# efr32_radio_interface.net
KiCad netlist of a schematic drawn in Altium Designer
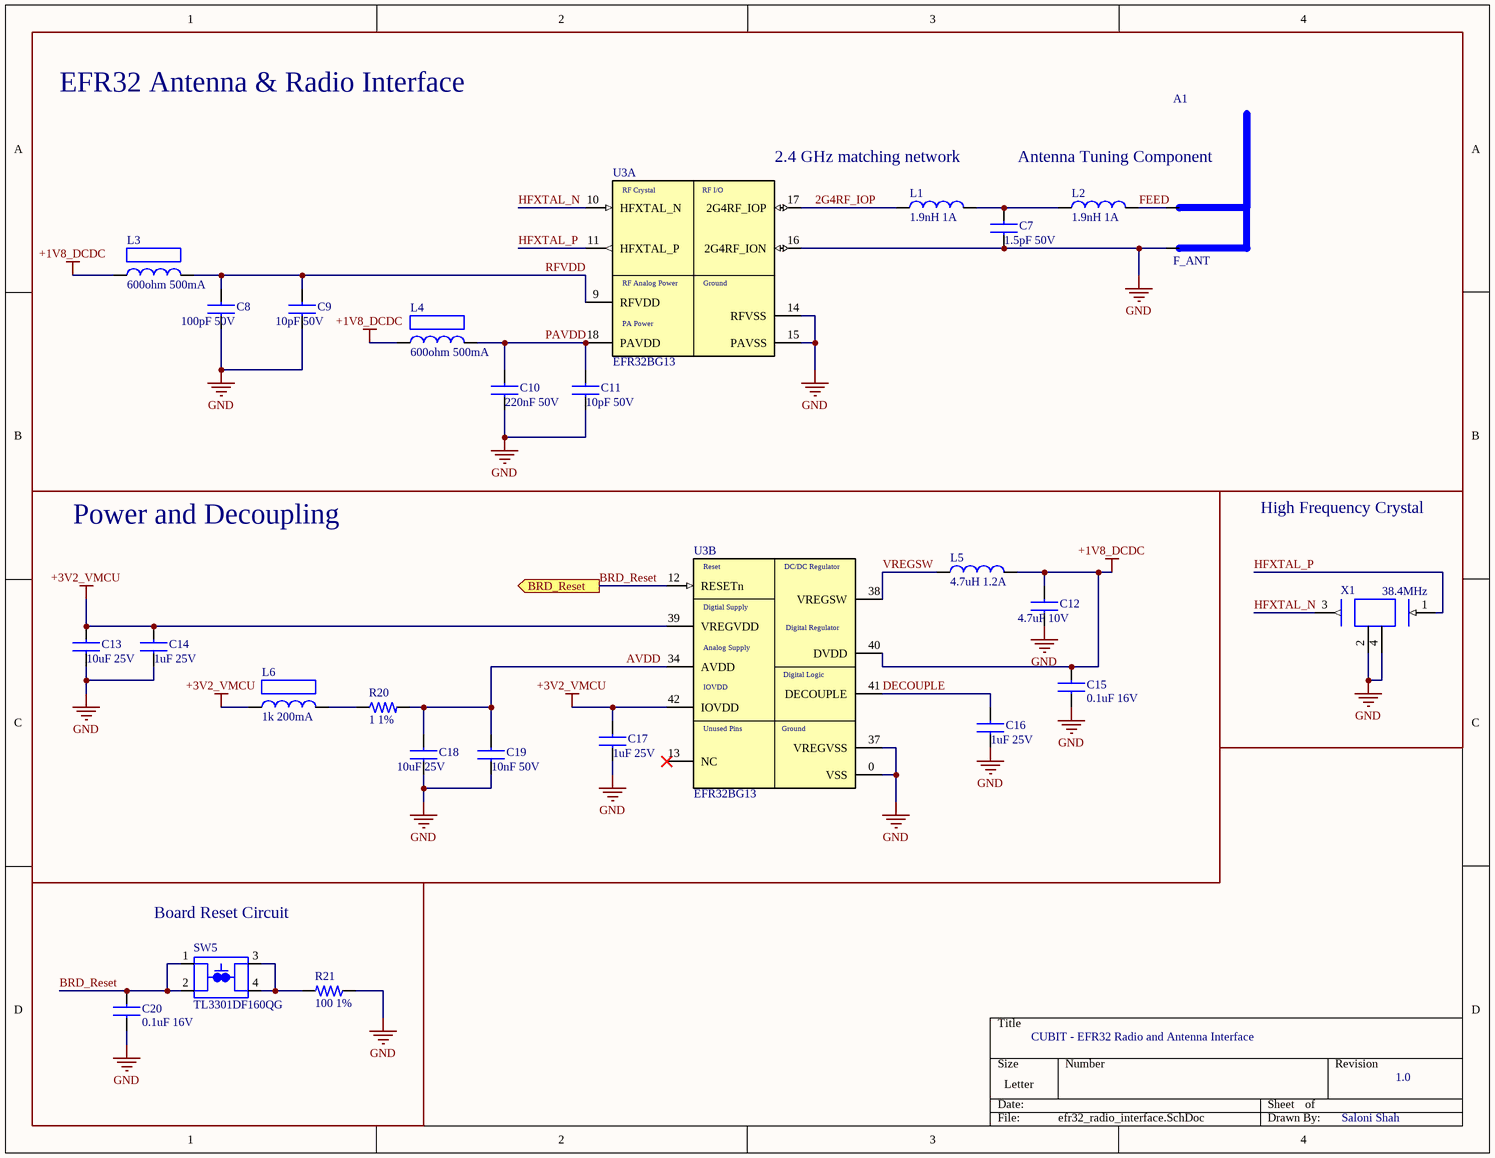
[diagram p0: efr32_radio_interface.SchDoc]

(export (version "E")
  (design (tool "Eeschema 10.0.6"))
  (components
    (comp (ref "A1")
      (value "F_ANT")
      (footprint "F_ANTENNA_FOOTPRINT")
      (libsource (lib "LPEDT_proj_lib") (part "F_ANT"))
    )
    (comp (ref "C7")
      (value "1.5pF 50V")
      (footprint "CAP_0402_1mm")
      (description "Cap Ceramic 1.5pF 50V C0G 5% Pad SMD 0402 125C Automotive T/R")
      (fields
        (field (name "MANUFACTURER") "Murata")
        (field (name "MANUFACTURER PART NUMBER") "GCM1555C1H1R5JA16D")
      )
      (libsource (lib "LPEDT_proj_lib") (part "GCM1555C1H1R5JA16D"))
    )
    (comp (ref "C8")
      (value "100pF 50V")
      (footprint "LPEDT_proj_lib:CAP_0805_02X125")
      (description "Cap 0.1nF ±10% 50V X7R 0805")
      (fields
        (field (name "MANUFACTURER") "Yageo")
        (field (name "MANUFACTURER PART NUMBER") "CC0805KRX7R9BB101")
      )
      (libsource (lib "LPEDT_proj_lib") (part "CC0805KRX7R9BB101"))
    )
    (comp (ref "C9")
      (value "10pF 50V")
      (footprint "LPEDT_proj_lib:CAP_0805_02X125")
      (description "Cap Ceramic 10pF 50V X7R 10% SMD 0805 125°C Paper T/R")
      (fields
        (field (name "MANUFACTURER") "KEMET")
        (field (name "MANUFACTURER PART NUMBER") "C0805C100K5RACTU")
      )
      (libsource (lib "LPEDT_proj_lib") (part "C0805C100K5RACTU"))
    )
    (comp (ref "C10")
      (value "220nF 50V")
      (footprint "LPEDT_proj_lib:CAP_0805_02X125")
      (description "Cap 220nF ±10% 50V X7R 0805")
      (fields
        (field (name "MANUFACTURER") "Yageo")
        (field (name "MANUFACTURER PART NUMBER") "CC0805KKX7R9BB224")
      )
      (libsource (lib "LPEDT_proj_lib") (part "CC0805KKX7R9BB224"))
    )
    (comp (ref "C11")
      (value "10pF 50V")
      (footprint "LPEDT_proj_lib:CAP_0805_02X125")
      (description "Cap Ceramic 10pF 50V X7R 10% SMD 0805 125°C Paper T/R")
      (fields
        (field (name "MANUFACTURER") "KEMET")
        (field (name "MANUFACTURER PART NUMBER") "C0805C100K5RACTU")
      )
      (libsource (lib "LPEDT_proj_lib") (part "C0805C100K5RACTU"))
    )
    (comp (ref "C12")
      (value "4.7uF 10V")
      (footprint "LPEDT_proj_lib:CAP_0603_1MM")
      (description "Cap CL10 Series 4.7 uF 10 V ±10 % Tolerance X5R SMT Multilayer Ceramic Capacitor")
      (fields
        (field (name "MANUFACTURER") "Samsung")
        (field (name "MANUFACTURER PART NUMBER") "CL10A475KP8NNNC")
      )
      (libsource (lib "LPEDT_proj_lib") (part "CL10A475KP8NNNC"))
    )
    (comp (ref "C13")
      (value "10uF 25V")
      (footprint "LPEDT_proj_lib:CAP_0805_02X125")
      (description "Cap 0805 25 V 10 uF ±20% Tolerance X5R Monolithic Ceramic Chip Capacitor")
      (fields
        (field (name "MANUFACTURER") "Murata")
        (field (name "MANUFACTURER PART NUMBER") "GRM21BR61E106KA73K")
      )
      (libsource (lib "LPEDT_proj_lib") (part "GRM21BR61E106KA73K"))
    )
    (comp (ref "C14")
      (value "1uF 25V")
      (footprint "LPEDT_proj_lib:CAP_0805_02X125")
      (description "Cap 1 µF ±10% 25V Ceramic Capacitor X5R 0805 (2012 Metric)")
      (fields
        (field (name "MANUFACTURER") "Murata")
        (field (name "MANUFACTURER PART NUMBER") "GRM216R61E105KA12D")
      )
      (libsource (lib "LPEDT_proj_lib") (part "GRM216R61E105KA12D"))
    )
    (comp (ref "C15")
      (value "0.1uF 16V")
      (footprint "LPEDT_proj_lib:CAP_0603_1MM")
      (description "Cap Ceramic 0.1uF 16V X7R 10% SMD 0603 125°C Paper T/R")
      (fields
        (field (name "MANUFACTURER") "KEMET")
        (field (name "MANUFACTURER PART NUMBER") "C0805C104K4RACAUTO")
      )
      (libsource (lib "LPEDT_proj_lib") (part "C0805C104K4RACAUTO"))
    )
    (comp (ref "C16")
      (value "1uF 25V")
      (footprint "LPEDT_proj_lib:CAP_0805_02X125")
      (description "Cap 1 µF ±10% 25V Ceramic Capacitor X5R 0805 (2012 Metric)")
      (fields
        (field (name "MANUFACTURER") "Murata")
        (field (name "MANUFACTURER PART NUMBER") "GRM216R61E105KA12D")
      )
      (libsource (lib "LPEDT_proj_lib") (part "GRM216R61E105KA12D"))
    )
    (comp (ref "C17")
      (value "1uF 25V")
      (footprint "LPEDT_proj_lib:CAP_0805_02X125")
      (description "Cap 1 µF ±10% 25V Ceramic Capacitor X5R 0805 (2012 Metric)")
      (fields
        (field (name "MANUFACTURER") "Murata")
        (field (name "MANUFACTURER PART NUMBER") "GRM216R61E105KA12D")
      )
      (libsource (lib "LPEDT_proj_lib") (part "GRM216R61E105KA12D"))
    )
    (comp (ref "C18")
      (value "10uF 25V")
      (footprint "LPEDT_proj_lib:CAP_0805_02X125")
      (description "Cap 0805 25 V 10 uF ±20% Tolerance X5R Monolithic Ceramic Chip Capacitor")
      (fields
        (field (name "MANUFACTURER") "Murata")
        (field (name "MANUFACTURER PART NUMBER") "GRM21BR61E106KA73K")
      )
      (libsource (lib "LPEDT_proj_lib") (part "GRM21BR61E106KA73K"))
    )
    (comp (ref "C19")
      (value "10nF 50V")
      (footprint "LPEDT_proj_lib:CAP_0805_02X125")
      (description "Cap 10nF ±10% 50V X7R 0805")
      (fields
        (field (name "MANUFACTURER") "Samsung")
        (field (name "MANUFACTURER PART NUMBER") "CL21B103KBCNNNC")
      )
      (libsource (lib "LPEDT_proj_lib") (part "CL21B103KBCNNNC"))
    )
    (comp (ref "C20")
      (value "0.1uF 16V")
      (footprint "LPEDT_proj_lib:CAP_0603_1MM")
      (description "Cap Ceramic 0.1uF 16V X7R 10% SMD 0603 125°C Paper T/R")
      (fields
        (field (name "MANUFACTURER") "KEMET")
        (field (name "MANUFACTURER PART NUMBER") "C0805C104K4RACAUTO")
      )
      (libsource (lib "LPEDT_proj_lib") (part "C0805C104K4RACAUTO"))
    )
    (comp (ref "L1")
      (value "1.9nH 1A")
      (footprint "CAP_0402_1mm")
      (description "Inductor Chip 1.9nH 0.3nH Tolerance 2-Pin 0402 Paper T/R")
      (fields
        (field (name "MANUFACTURER") "Murata")
        (field (name "MANUFACTURER PART NUMBER") "LQG15WZ1N9S02D")
      )
      (libsource (lib "LPEDT_proj_lib") (part "LQG15WZ1N9S02D"))
    )
    (comp (ref "L2")
      (value "1.9nH 1A")
      (footprint "CAP_0402_1mm")
      (description "Inductor Chip 1.9nH 0.3nH Tolerance 2-Pin 0402 Paper T/R")
      (fields
        (field (name "MANUFACTURER") "Murata")
        (field (name "MANUFACTURER PART NUMBER") "LQG15WZ1N9S02D")
      )
      (libsource (lib "LPEDT_proj_lib") (part "LQG15WZ1N9S02D"))
    )
    (comp (ref "L3")
      (value "600ohm 500mA")
      (footprint "IND_FERRITE_0603_1.6x0.4")
      (description "Ferrite Beads 0603 600Ω ±25% DCR=0.38Ω 500mA")
      (fields
        (field (name "MANUFACTURER") "Murata")
        (field (name "MANUFACTURER PART NUMBER") "BLM18AG601SN1D")
      )
      (libsource (lib "LPEDT_proj_lib") (part "BLM18AG601SN1D"))
    )
    (comp (ref "L4")
      (value "600ohm 500mA")
      (footprint "IND_FERRITE_0603_1.6x0.4")
      (description "Ferrite Beads 0603 600Ω ±25% DCR=0.38Ω 500mA")
      (fields
        (field (name "MANUFACTURER") "Murata")
        (field (name "MANUFACTURER PART NUMBER") "BLM18AG601SN1D")
      )
      (libsource (lib "LPEDT_proj_lib") (part "BLM18AG601SN1D"))
    )
    (comp (ref "L5")
      (value "4.7uH 1.2A")
      (footprint "2_IND_32X25")
      (description "Inductor FIXED IND 4.7UH 1.2A 186 MOHM")
      (fields
        (field (name "MANUFACTURER") "Murata")
        (field (name "MANUFACTURER PART NUMBER") "LQH32PH4R7NNCL")
      )
      (libsource (lib "LPEDT_proj_lib") (part "LQH32PH4R7NNCL"))
    )
    (comp (ref "L6")
      (value "1k 200mA")
      (footprint "LPEDT_proj_lib:CAP_0603_1MM")
      (description "Ferrite Beads WE-CBF 0603 SMD Bead 100MHz 1000Ohm 200mA")
      (fields
        (field (name "MANUFACTURER") "Wurth Electronics")
        (field (name "MANUFACTURER PART NUMBER") "74279266")
      )
      (libsource (lib "LPEDT_proj_lib") (part "74279266"))
    )
    (comp (ref "R20")
      (value "1 1%")
      (footprint "LPEDT_proj_lib:CAP_0603_1MM")
      (description "Res 1 Ohm 1% 1/10W ±200ppm/°C Molded SMD SMD Paper T/R")
      (fields
        (field (name "MANUFACTURER") "Yageo")
        (field (name "MANUFACTURER PART NUMBER") "RC0603FR-101RL")
      )
      (libsource (lib "LPEDT_proj_lib") (part "RC0603FR-101RL"))
    )
    (comp (ref "R21")
      (value "100 1%")
      (footprint "2_Chip_0603_RMCF")
      (description "Res 100 Ohm 1% 1/10W ±100ppm/°C Molded SMD SMD Paper T/R")
      (fields
        (field (name "MANUFACTURER") "Stackpole Electronics")
        (field (name "MANUFACTURER PART NUMBER") "RMCF0603FT100R")
      )
      (libsource (lib "LPEDT_proj_lib") (part "RMCF0603FT100R"))
    )
    (comp (ref "SW5")
      (value "TL3301DF160QG")
      (footprint "SW_TL3301DF160QG")
      (description "Tactile Switch SPST-NO Top Actuated Surface Mount")
      (fields (field (name "MF") "E-Switch"))
      (libsource (lib "LPEDT_proj_lib") (part "TL3301DF160QG"))
    )
    (comp (ref "U3")
      (value "EFR32BG13")
      (footprint "48-QFN_7x7")
      (description "Blue Gecko QFN48 2.4 G 19 dB BLE/Proprietary 512 kB 64 kB(RAM) 31GPIO")
      (fields
        (field (name "MANUFACTURER") "Silicon Labs")
        (field (name "MANUFACTURER PART NUMBER") "EFR32BG13P732F512GM48-D")
      )
      (libsource (lib "LPEDT_proj_lib") (part "EFR32BG13P732F512GM48-D"))
    )
    (comp (ref "X1")
      (value "38.4MHz")
      (footprint "OSC_38.4MHz")
      (description "Crystal 38.4000MHZ 10PF SMD")
      (fields
        (field (name "MANUFACTURER") "Raltron Electronics")
        (field (name "MANUFACTURER PART NUMBER") "RH100-38.400-10-F-1010-TR")
      )
      (libsource (lib "LPEDT_proj_lib") (part "RH100-38.400-10-F-1010-TR"))
    )
  )
  (nets
    (net (code "1") (name "+1V8_DCDC") (class "Default")
      (node (ref "C12") (pin "1") (pinfunction "1_1") (pintype "passive"))
      (node (ref "C15") (pin "1") (pinfunction "1_1") (pintype "passive"))
      (node (ref "L3") (pin "1") (pinfunction "1_1") (pintype "passive"))
      (node (ref "L4") (pin "1") (pinfunction "1_1") (pintype "passive"))
      (node (ref "L5") (pin "2") (pinfunction "2_2") (pintype "passive"))
      (node (ref "U3") (pin "40") (pinfunction "DVDD_40") (pintype "power_in"))
    )
    (net (code "2") (name "+3V2_VMCU") (class "Default")
      (node (ref "C13") (pin "1") (pinfunction "1_1") (pintype "passive"))
      (node (ref "C14") (pin "1") (pinfunction "1_1") (pintype "passive"))
      (node (ref "C17") (pin "1") (pinfunction "1_1") (pintype "passive"))
      (node (ref "L6") (pin "1") (pinfunction "1_1") (pintype "passive"))
      (node (ref "U3") (pin "39") (pinfunction "VREGVDD_39") (pintype "power_in"))
      (node (ref "U3") (pin "42") (pinfunction "IOVDD_42") (pintype "power_in"))
    )
    (net (code "3") (name "/2G4RF_IOP") (class "Default")
      (node (ref "L1") (pin "1") (pinfunction "1_1") (pintype "passive"))
      (node (ref "U3") (pin "17") (pinfunction "2G4RF_IOP_17") (pintype "bidirectional"))
    )
    (net (code "4") (name "/AVDD") (class "Default")
      (node (ref "C18") (pin "1") (pinfunction "1_1") (pintype "passive"))
      (node (ref "C19") (pin "1") (pinfunction "1_1") (pintype "passive"))
      (node (ref "R20") (pin "2") (pinfunction "2_2") (pintype "passive"))
      (node (ref "U3") (pin "34") (pinfunction "AVDD_34") (pintype "power_in"))
    )
    (net (code "5") (name "/BRD_Reset") (class "Default")
      (node (ref "C20") (pin "1") (pinfunction "1_1") (pintype "passive"))
      (node (ref "SW5") (pin "1") (pinfunction "1_1") (pintype "passive"))
      (node (ref "SW5") (pin "2") (pinfunction "2_2") (pintype "passive"))
      (node (ref "U3") (pin "12") (pinfunction "RESETn_12") (pintype "input"))
    )
    (net (code "6") (name "/DECOUPLE") (class "Default")
      (node (ref "C16") (pin "1") (pinfunction "1_1") (pintype "passive"))
      (node (ref "U3") (pin "41") (pinfunction "DECOUPLE_41") (pintype "power_in"))
    )
    (net (code "7") (name "/FEED") (class "Default")
      (node (ref "A1") (pin "FEED") (pinfunction "FEED_FEED") (pintype "passive"))
      (node (ref "L2") (pin "2") (pinfunction "2_2") (pintype "passive"))
    )
    (net (code "8") (name "/HFXTAL_N") (class "Default")
      (node (ref "U3") (pin "10") (pinfunction "HFXTAL_N_10") (pintype "input"))
      (node (ref "X1") (pin "3") (pintype "output"))
    )
    (net (code "9") (name "/HFXTAL_P") (class "Default")
      (node (ref "U3") (pin "11") (pinfunction "HFXTAL_P_11") (pintype "output"))
      (node (ref "X1") (pin "1") (pintype "input"))
    )
    (net (code "10") (name "/PAVDD") (class "Default")
      (node (ref "C10") (pin "1") (pinfunction "1_1") (pintype "passive"))
      (node (ref "C11") (pin "1") (pinfunction "1_1") (pintype "passive"))
      (node (ref "L4") (pin "2") (pinfunction "2_2") (pintype "passive"))
      (node (ref "U3") (pin "18") (pinfunction "PAVDD_18") (pintype "power_in"))
    )
    (net (code "11") (name "/RFVDD") (class "Default")
      (node (ref "C8") (pin "1") (pinfunction "1_1") (pintype "passive"))
      (node (ref "C9") (pin "1") (pinfunction "1_1") (pintype "passive"))
      (node (ref "L3") (pin "2") (pinfunction "2_2") (pintype "passive"))
      (node (ref "U3") (pin "9") (pinfunction "RFVDD_9") (pintype "power_in"))
    )
    (net (code "12") (name "/VREGSW") (class "Default")
      (node (ref "L5") (pin "1") (pinfunction "1_1") (pintype "passive"))
      (node (ref "U3") (pin "38") (pinfunction "VREGSW_38") (pintype "power_in"))
    )
    (net (code "13") (name "GND") (class "Default")
      (node (ref "A1") (pin "GND") (pinfunction "GND_GND") (pintype "passive"))
      (node (ref "C10") (pin "2") (pinfunction "2_2") (pintype "passive"))
      (node (ref "C11") (pin "2") (pinfunction "2_2") (pintype "passive"))
      (node (ref "C12") (pin "2") (pinfunction "2_2") (pintype "passive"))
      (node (ref "C13") (pin "2") (pinfunction "2_2") (pintype "passive"))
      (node (ref "C14") (pin "2") (pinfunction "2_2") (pintype "passive"))
      (node (ref "C15") (pin "2") (pinfunction "2_2") (pintype "passive"))
      (node (ref "C16") (pin "2") (pinfunction "2_2") (pintype "passive"))
      (node (ref "C17") (pin "2") (pinfunction "2_2") (pintype "passive"))
      (node (ref "C18") (pin "2") (pinfunction "2_2") (pintype "passive"))
      (node (ref "C19") (pin "2") (pinfunction "2_2") (pintype "passive"))
      (node (ref "C20") (pin "2") (pinfunction "2_2") (pintype "passive"))
      (node (ref "C7") (pin "2") (pinfunction "2_2") (pintype "passive"))
      (node (ref "C8") (pin "2") (pinfunction "2_2") (pintype "passive"))
      (node (ref "C9") (pin "2") (pinfunction "2_2") (pintype "passive"))
      (node (ref "R21") (pin "1") (pinfunction "1_1") (pintype "passive"))
      (node (ref "U3") (pin "0") (pinfunction "VSS_0") (pintype "power_in"))
      (node (ref "U3") (pin "14") (pinfunction "RFVSS_14") (pintype "power_in"))
      (node (ref "U3") (pin "15") (pinfunction "PAVSS_15") (pintype "power_in"))
      (node (ref "U3") (pin "16") (pinfunction "2G4RF_ION_16") (pintype "bidirectional"))
      (node (ref "U3") (pin "37") (pinfunction "VREGVSS_37") (pintype "power_in"))
      (node (ref "X1") (pin "2") (pintype "power_in"))
      (node (ref "X1") (pin "4") (pintype "power_in"))
    )
    (net (code "14") (name "Net-(C7-Pad1)") (class "Default")
      (node (ref "C7") (pin "1") (pinfunction "1_1") (pintype "passive"))
      (node (ref "L1") (pin "2") (pinfunction "2_2") (pintype "passive"))
      (node (ref "L2") (pin "1") (pinfunction "1_1") (pintype "passive"))
    )
    (net (code "15") (name "Net-(L6-Pad2)") (class "Default")
      (node (ref "L6") (pin "2") (pinfunction "2_2") (pintype "passive"))
      (node (ref "R20") (pin "1") (pinfunction "1_1") (pintype "passive"))
    )
    (net (code "16") (name "Net-(R21-Pad2)") (class "Default")
      (node (ref "R21") (pin "2") (pinfunction "2_2") (pintype "passive"))
      (node (ref "SW5") (pin "3") (pinfunction "3_3") (pintype "passive"))
      (node (ref "SW5") (pin "4") (pinfunction "4_4") (pintype "passive"))
    )
    (net (code "17") (name "unconnected-(U3B-NC-Pad13)") (class "Default")
      (node (ref "U3") (pin "13") (pinfunction "NC_13") (pintype "passive+no_connect"))
    )
  )
)
